# Sheet2.net
KiCad netlist of a schematic drawn in Altium Designer
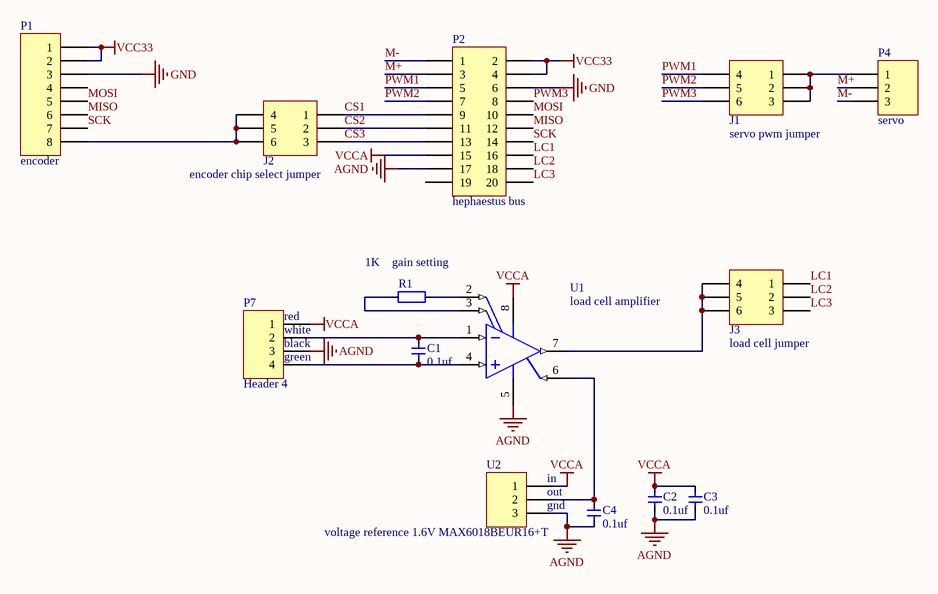
[diagram p0: Sheet2.SchDoc]

(export (version "E")
  (design (tool "Eeschema 10.0.6"))
  (components
    (comp (ref "C1")
      (value "0.1uf")
      (footprint "PCB_PassiveCap:CAP_0805")
      (description "Capacitor")
      (fields (field (name "Comment") "Cap_0805"))
      (libsource (lib "SCH_Passive") (part "Cap_0805"))
    )
    (comp (ref "C2")
      (value "0.1uf")
      (footprint "PCB_PassiveCap:CAP_0805")
      (description "Capacitor")
      (fields (field (name "Comment") "Cap_0805"))
      (libsource (lib "SCH_Passive") (part "Cap_0805"))
    )
    (comp (ref "C3")
      (value "0.1uf")
      (footprint "PCB_PassiveCap:CAP_0805")
      (description "Capacitor")
      (fields (field (name "Comment") "Cap_0805"))
      (libsource (lib "SCH_Passive") (part "Cap_0805"))
    )
    (comp (ref "C4")
      (value "0.1uf")
      (footprint "PCB_PassiveCap:CAP_0805")
      (description "Capacitor")
      (fields (field (name "Comment") "Cap_0805"))
      (libsource (lib "SCH_Passive") (part "Cap_0805"))
    )
    (comp (ref "J1")
      (value "servo pwm jumper")
      (footprint "61300621121")
      (description "WR-PHD 2.54 mm THT Dual Pin Header, 06p")
      (fields (field (name "PARTNUMBER") "61300621121") (field (name "PUBLISHER") "Wurth Elektronik"))
      (libsource (lib "ALTIUM-PHD_2_54_THT_PIN_HEADER_6130XX11121-rev16c") (part "61300621121"))
    )
    (comp (ref "J2")
      (value "encoder chip select jumper")
      (footprint "61300621121")
      (description "WR-PHD 2.54 mm THT Dual Pin Header, 06p")
      (fields (field (name "PARTNUMBER") "61300621121") (field (name "PUBLISHER") "Wurth Elektronik"))
      (libsource (lib "ALTIUM-PHD_2_54_THT_PIN_HEADER_6130XX11121-rev16c") (part "61300621121"))
    )
    (comp (ref "J3")
      (value "load cell jumper")
      (footprint "61300621121")
      (description "WR-PHD 2.54 mm THT Dual Pin Header, 06p")
      (fields (field (name "PARTNUMBER") "61300621121") (field (name "PUBLISHER") "Wurth Elektronik"))
      (libsource (lib "ALTIUM-PHD_2_54_THT_PIN_HEADER_6130XX11121-rev16c") (part "61300621121"))
    )
    (comp (ref "P1")
      (value "encoder")
      (footprint "HDR1X8")
      (description "Header, 8-Pin")
      (fields (field (name "PUBLISHER") "Altium Limited"))
      (libsource (lib "Miscellaneous Connectors") (part "Header 8"))
    )
    (comp (ref "P2")
      (value "hephaestus bus")
      (footprint "612020235121")
      (description "WR-BHD 2.54mm Male Box Header High Temperature")
      (fields
        (field (name "MANUFACTURER") "Wurth Elektronik")
        (field (name "PARTNO") "612020235121")
        (field (name "CREATED BY") "Baojun Chen")
      )
      (libsource (lib "ALTIUM-BHD_2_54_MALE_BOX_HEADER_6120XX21621-rev16b") (part "612020235121"))
    )
    (comp (ref "P4")
      (value "servo")
      (footprint "HDR1X3")
      (description "Header, 3-Pin")
      (fields (field (name "PUBLISHER") "Altium Limited"))
      (libsource (lib "") (part "Header 3_1"))
    )
    (comp (ref "P7")
      (value "Header 4")
      (footprint "HDR1X4")
      (description "Header, 4-Pin")
      (fields (field (name "PUBLISHER") "Altium Limited"))
      (libsource (lib "Miscellaneous Connectors") (part "Header 4"))
    )
    (comp (ref "R1")
      (value "gain setting")
      (footprint "PCB_PassiveRes:RES_0805")
      (description "Resistor")
      (fields (field (name "ALTIUM_VALUE") "1K"))
      (libsource (lib "SCH_Passive") (part "Res_0805"))
    )
    (comp (ref "U1")
      (value "load cell amplifier")
      (footprint "TI-D8_N")
      (fields (field (name "MANUFACTURER") "Texas Instruments") (field (name "PARTNUMBER") "INA826AIDR"))
      (libsource (lib "TI Amplifiers and Linear Instrumentation Amplifier") (part "INA826AIDR"))
    )
    (comp (ref "U2")
      (value "voltage reference 1.6V MAX6018BEUR16+T")
      (footprint "SOT23-3")
      (description "MAX6018BEUR16+T")
      (fields (field (name "PUBLISHER") "Altium Limited"))
      (libsource (lib "Miscellaneous Connectors") (part "Header 3"))
    )
  )
  (nets
    (net (code "1") (name "/CS1") (class "Default")
      (node (ref "J2") (pin "1") (pinfunction "1_1") (pintype "passive"))
      (node (ref "P2") (pin "9") (pinfunction "9_9") (pintype "passive"))
    )
    (net (code "2") (name "/CS2") (class "Default")
      (node (ref "J2") (pin "2") (pinfunction "2_2") (pintype "passive"))
      (node (ref "P2") (pin "11") (pinfunction "11_11") (pintype "passive"))
    )
    (net (code "3") (name "/CS3") (class "Default")
      (node (ref "J2") (pin "3") (pinfunction "3_3") (pintype "passive"))
      (node (ref "P2") (pin "13") (pinfunction "13_13") (pintype "passive"))
    )
    (net (code "4") (name "/LC1") (class "Default")
      (node (ref "J3") (pin "1") (pinfunction "1_1") (pintype "passive"))
      (node (ref "P2") (pin "16") (pinfunction "16_16") (pintype "passive"))
    )
    (net (code "5") (name "/LC2") (class "Default")
      (node (ref "J3") (pin "2") (pinfunction "2_2") (pintype "passive"))
      (node (ref "P2") (pin "18") (pinfunction "18_18") (pintype "passive"))
    )
    (net (code "6") (name "/LC3") (class "Default")
      (node (ref "J3") (pin "3") (pinfunction "3_3") (pintype "passive"))
      (node (ref "P2") (pin "20") (pinfunction "20_20") (pintype "passive"))
    )
    (net (code "7") (name "/M+") (class "Default")
      (node (ref "P2") (pin "3") (pinfunction "3_3") (pintype "passive"))
      (node (ref "P4") (pin "2") (pinfunction "2_2") (pintype "passive"))
    )
    (net (code "8") (name "/M-") (class "Default")
      (node (ref "P2") (pin "1") (pinfunction "1_1") (pintype "passive"))
      (node (ref "P4") (pin "3") (pinfunction "3_3") (pintype "passive"))
    )
    (net (code "9") (name "/MISO") (class "Default")
      (node (ref "P1") (pin "6") (pinfunction "6_6") (pintype "passive"))
      (node (ref "P2") (pin "12") (pinfunction "12_12") (pintype "passive"))
    )
    (net (code "10") (name "/MOSI") (class "Default")
      (node (ref "P1") (pin "5") (pinfunction "5_5") (pintype "passive"))
      (node (ref "P2") (pin "10") (pinfunction "10_10") (pintype "passive"))
    )
    (net (code "11") (name "/PWM1") (class "Default")
      (node (ref "J1") (pin "4") (pinfunction "4_4") (pintype "passive"))
      (node (ref "P2") (pin "5") (pinfunction "5_5") (pintype "passive"))
    )
    (net (code "12") (name "/PWM2") (class "Default")
      (node (ref "J1") (pin "5") (pinfunction "5_5") (pintype "passive"))
      (node (ref "P2") (pin "7") (pinfunction "7_7") (pintype "passive"))
    )
    (net (code "13") (name "/PWM3") (class "Default")
      (node (ref "J1") (pin "6") (pinfunction "6_6") (pintype "passive"))
      (node (ref "P2") (pin "8") (pinfunction "8_8") (pintype "passive"))
    )
    (net (code "14") (name "/SCK") (class "Default")
      (node (ref "P1") (pin "7") (pinfunction "7_7") (pintype "passive"))
      (node (ref "P2") (pin "14") (pinfunction "14_14") (pintype "passive"))
    )
    (net (code "15") (name "AGND") (class "Default")
      (node (ref "C2") (pin "2") (pinfunction "2_2") (pintype "passive"))
      (node (ref "C3") (pin "2") (pinfunction "2_2") (pintype "passive"))
      (node (ref "C4") (pin "2") (pinfunction "2_2") (pintype "passive"))
      (node (ref "P2") (pin "17") (pinfunction "17_17") (pintype "passive"))
      (node (ref "P7") (pin "3") (pinfunction "3_3") (pintype "passive"))
      (node (ref "U1") (pin "5") (pinfunction "VS-_5") (pintype "power_in"))
      (node (ref "U2") (pin "3") (pinfunction "3_3") (pintype "passive"))
    )
    (net (code "16") (name "GND") (class "Default")
      (node (ref "P1") (pin "3") (pinfunction "3_3") (pintype "passive"))
      (node (ref "P2") (pin "6") (pinfunction "6_6") (pintype "passive"))
    )
    (net (code "17") (name "Net-(J1-Pad1)") (class "Default")
      (node (ref "J1") (pin "1") (pinfunction "1_1") (pintype "passive"))
      (node (ref "J1") (pin "2") (pinfunction "2_2") (pintype "passive"))
      (node (ref "J1") (pin "3") (pinfunction "3_3") (pintype "passive"))
      (node (ref "P4") (pin "1") (pinfunction "1_1") (pintype "passive"))
    )
    (net (code "18") (name "Net-(J2-Pad4)") (class "Default")
      (node (ref "J2") (pin "4") (pinfunction "4_4") (pintype "passive"))
      (node (ref "J2") (pin "5") (pinfunction "5_5") (pintype "passive"))
      (node (ref "J2") (pin "6") (pinfunction "6_6") (pintype "passive"))
      (node (ref "P1") (pin "8") (pinfunction "8_8") (pintype "passive"))
    )
    (net (code "19") (name "Net-(R1-Pad1)") (class "Default")
      (node (ref "R1") (pin "1") (pinfunction "1_1") (pintype "passive"))
      (node (ref "U1") (pin "2") (pinfunction "RG_2") (pintype "input"))
    )
    (net (code "20") (name "Net-(R1-Pad2)") (class "Default")
      (node (ref "R1") (pin "2") (pinfunction "2_2") (pintype "passive"))
      (node (ref "U1") (pin "3") (pinfunction "RG_3") (pintype "input"))
    )
    (net (code "21") (name "Net-(U1-IN+)") (class "Default")
      (node (ref "C1") (pin "2") (pinfunction "2_2") (pintype "passive"))
      (node (ref "P7") (pin "4") (pinfunction "4_4") (pintype "passive"))
      (node (ref "U1") (pin "4") (pinfunction "IN+_4") (pintype "input"))
    )
    (net (code "22") (name "Net-(U1-IN-)") (class "Default")
      (node (ref "C1") (pin "1") (pinfunction "1_1") (pintype "passive"))
      (node (ref "P7") (pin "2") (pinfunction "2_2") (pintype "passive"))
      (node (ref "U1") (pin "1") (pinfunction "IN-_1") (pintype "input"))
    )
    (net (code "23") (name "Net-(U1-REF)") (class "Default")
      (node (ref "C4") (pin "1") (pinfunction "1_1") (pintype "passive"))
      (node (ref "U1") (pin "6") (pinfunction "REF_6") (pintype "input"))
      (node (ref "U2") (pin "2") (pinfunction "2_2") (pintype "passive"))
    )
    (net (code "24") (name "Net-(U1-VOUT)") (class "Default")
      (node (ref "J3") (pin "4") (pinfunction "4_4") (pintype "passive"))
      (node (ref "J3") (pin "5") (pinfunction "5_5") (pintype "passive"))
      (node (ref "J3") (pin "6") (pinfunction "6_6") (pintype "passive"))
      (node (ref "U1") (pin "7") (pinfunction "VOUT_7") (pintype "output"))
    )
    (net (code "25") (name "VCC33") (class "Default")
      (node (ref "P1") (pin "1") (pinfunction "1_1") (pintype "passive"))
      (node (ref "P1") (pin "2") (pinfunction "2_2") (pintype "passive"))
      (node (ref "P2") (pin "2") (pinfunction "2_2") (pintype "passive"))
      (node (ref "P2") (pin "4") (pinfunction "4_4") (pintype "passive"))
    )
    (net (code "26") (name "VCCA") (class "Default")
      (node (ref "C2") (pin "1") (pinfunction "1_1") (pintype "passive"))
      (node (ref "C3") (pin "1") (pinfunction "1_1") (pintype "passive"))
      (node (ref "P2") (pin "15") (pinfunction "15_15") (pintype "passive"))
      (node (ref "P7") (pin "1") (pinfunction "1_1") (pintype "passive"))
      (node (ref "U1") (pin "8") (pinfunction "VS+_8") (pintype "power_in"))
      (node (ref "U2") (pin "1") (pinfunction "1_1") (pintype "passive"))
    )
    (net (code "27") (name "unconnected-(P1-Pad4)") (class "Default")
      (node (ref "P1") (pin "4") (pinfunction "4_4") (pintype "passive"))
    )
    (net (code "28") (name "unconnected-(P2-Pad19)") (class "Default")
      (node (ref "P2") (pin "19") (pinfunction "19_19") (pintype "passive"))
    )
  )
)
